# InterfacesB_NONISO232a.net
KiCad netlist of a schematic drawn in Altium Designer
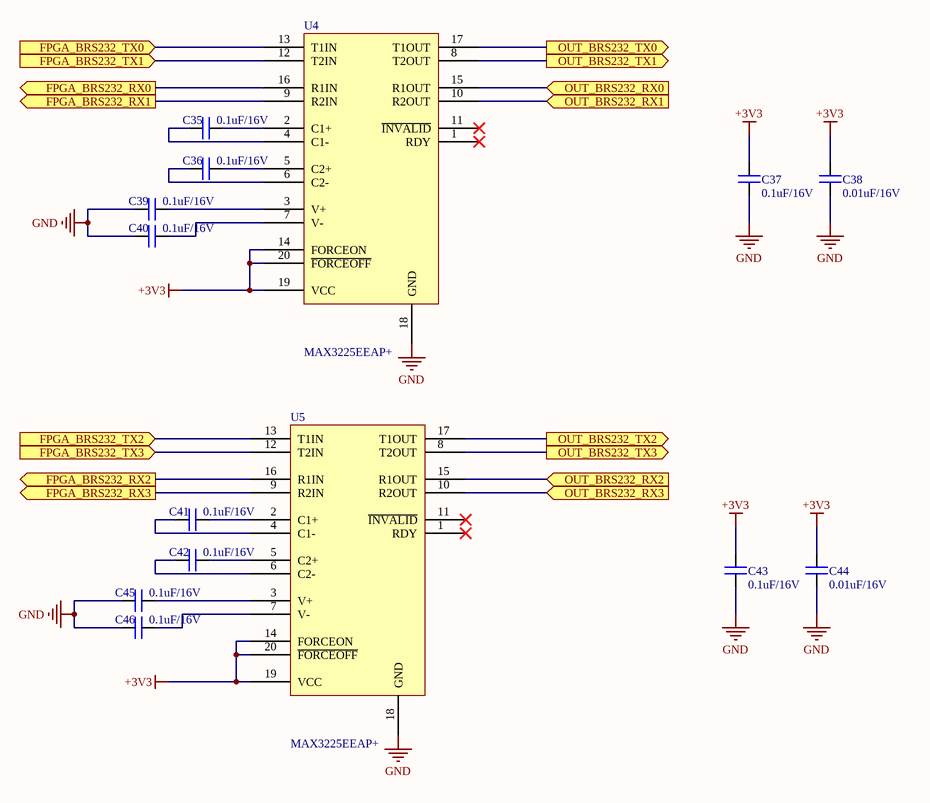
[diagram p0: InterfacesB_NONISO232a.SchDoc]

(export (version "E")
  (design (tool "Eeschema 10.0.6"))
  (components
    (comp (ref "C35")
      (value "0.1uF/16V")
      (footprint "CAP_0805")
      (fields (field (name "Comment") "CAP_0805"))
      (libsource (lib "AdapterLib") (part "CAP_0805"))
    )
    (comp (ref "C36")
      (value "0.1uF/16V")
      (footprint "CAP_0805")
      (fields (field (name "Comment") "CAP_0805"))
      (libsource (lib "AdapterLib") (part "CAP_0805"))
    )
    (comp (ref "C37")
      (value "0.1uF/16V")
      (footprint "CAP_0805")
      (fields (field (name "Comment") "CAP_0805"))
      (libsource (lib "AdapterLib") (part "CAP_0805"))
    )
    (comp (ref "C38")
      (value "0.01uF/16V")
      (footprint "CAP_0805")
      (fields (field (name "Comment") "CAP_0805"))
      (libsource (lib "AdapterLib") (part "CAP_0805"))
    )
    (comp (ref "C39")
      (value "0.1uF/16V")
      (footprint "CAP_0805")
      (fields (field (name "Comment") "CAP_0805"))
      (libsource (lib "AdapterLib") (part "CAP_0805"))
    )
    (comp (ref "C40")
      (value "0.1uF/16V")
      (footprint "CAP_0805")
      (fields (field (name "Comment") "CAP_0805"))
      (libsource (lib "AdapterLib") (part "CAP_0805"))
    )
    (comp (ref "C41")
      (value "0.1uF/16V")
      (footprint "CAP_0805")
      (fields (field (name "Comment") "CAP_0805"))
      (libsource (lib "AdapterLib") (part "CAP_0805"))
    )
    (comp (ref "C42")
      (value "0.1uF/16V")
      (footprint "CAP_0805")
      (fields (field (name "Comment") "CAP_0805"))
      (libsource (lib "AdapterLib") (part "CAP_0805"))
    )
    (comp (ref "C43")
      (value "0.1uF/16V")
      (footprint "CAP_0805")
      (fields (field (name "Comment") "CAP_0805"))
      (libsource (lib "AdapterLib") (part "CAP_0805"))
    )
    (comp (ref "C44")
      (value "0.01uF/16V")
      (footprint "CAP_0805")
      (fields (field (name "Comment") "CAP_0805"))
      (libsource (lib "AdapterLib") (part "CAP_0805"))
    )
    (comp (ref "C45")
      (value "0.1uF/16V")
      (footprint "CAP_0805")
      (fields (field (name "Comment") "CAP_0805"))
      (libsource (lib "AdapterLib") (part "CAP_0805"))
    )
    (comp (ref "C46")
      (value "0.1uF/16V")
      (footprint "CAP_0805")
      (fields (field (name "Comment") "CAP_0805"))
      (libsource (lib "AdapterLib") (part "CAP_0805"))
    )
    (comp (ref "U4")
      (value "MAX3225EEAP+")
      (footprint "MAX3225EEAP+")
      (libsource (lib "AdapterLib") (part "MAX3225EEAP+"))
    )
    (comp (ref "U5")
      (value "MAX3225EEAP+")
      (footprint "MAX3225EEAP+")
      (libsource (lib "AdapterLib") (part "MAX3225EEAP+"))
    )
  )
  (nets
    (net (code "1") (name "+3V3") (class "Default")
      (node (ref "C37") (pin "1") (pinfunction "1_1") (pintype "passive"))
      (node (ref "C38") (pin "1") (pinfunction "1_1") (pintype "passive"))
      (node (ref "C43") (pin "1") (pinfunction "1_1") (pintype "passive"))
      (node (ref "C44") (pin "1") (pinfunction "1_1") (pintype "passive"))
      (node (ref "U4") (pin "14") (pinfunction "FORCEON_14") (pintype "passive"))
      (node (ref "U4") (pin "19") (pinfunction "VCC_19") (pintype "passive"))
      (node (ref "U4") (pin "20") (pinfunction "~{FORCEOFF}_20") (pintype "passive"))
      (node (ref "U5") (pin "14") (pinfunction "FORCEON_14") (pintype "passive"))
      (node (ref "U5") (pin "19") (pinfunction "VCC_19") (pintype "passive"))
      (node (ref "U5") (pin "20") (pinfunction "~{FORCEOFF}_20") (pintype "passive"))
    )
    (net (code "2") (name "/FPGA_BRS232_RX0") (class "Default")
      (node (ref "U4") (pin "16") (pinfunction "R1IN_16") (pintype "passive"))
    )
    (net (code "3") (name "/FPGA_BRS232_RX1") (class "Default")
      (node (ref "U4") (pin "9") (pinfunction "R2IN_9") (pintype "passive"))
    )
    (net (code "4") (name "/FPGA_BRS232_RX2") (class "Default")
      (node (ref "U5") (pin "16") (pinfunction "R1IN_16") (pintype "passive"))
    )
    (net (code "5") (name "/FPGA_BRS232_RX3") (class "Default")
      (node (ref "U5") (pin "9") (pinfunction "R2IN_9") (pintype "passive"))
    )
    (net (code "6") (name "/FPGA_BRS232_TX0") (class "Default")
      (node (ref "U4") (pin "13") (pinfunction "T1IN_13") (pintype "passive"))
    )
    (net (code "7") (name "/FPGA_BRS232_TX1") (class "Default")
      (node (ref "U4") (pin "12") (pinfunction "T2IN_12") (pintype "passive"))
    )
    (net (code "8") (name "/FPGA_BRS232_TX2") (class "Default")
      (node (ref "U5") (pin "13") (pinfunction "T1IN_13") (pintype "passive"))
    )
    (net (code "9") (name "/FPGA_BRS232_TX3") (class "Default")
      (node (ref "U5") (pin "12") (pinfunction "T2IN_12") (pintype "passive"))
    )
    (net (code "10") (name "/OUT_BRS232_RX0") (class "Default")
      (node (ref "U4") (pin "15") (pinfunction "R1OUT_15") (pintype "passive"))
    )
    (net (code "11") (name "/OUT_BRS232_RX1") (class "Default")
      (node (ref "U4") (pin "10") (pinfunction "R2OUT_10") (pintype "passive"))
    )
    (net (code "12") (name "/OUT_BRS232_RX2") (class "Default")
      (node (ref "U5") (pin "15") (pinfunction "R1OUT_15") (pintype "passive"))
    )
    (net (code "13") (name "/OUT_BRS232_RX3") (class "Default")
      (node (ref "U5") (pin "10") (pinfunction "R2OUT_10") (pintype "passive"))
    )
    (net (code "14") (name "/OUT_BRS232_TX0") (class "Default")
      (node (ref "U4") (pin "17") (pinfunction "T1OUT_17") (pintype "passive"))
    )
    (net (code "15") (name "/OUT_BRS232_TX1") (class "Default")
      (node (ref "U4") (pin "8") (pinfunction "T2OUT_8") (pintype "passive"))
    )
    (net (code "16") (name "/OUT_BRS232_TX2") (class "Default")
      (node (ref "U5") (pin "17") (pinfunction "T1OUT_17") (pintype "passive"))
    )
    (net (code "17") (name "/OUT_BRS232_TX3") (class "Default")
      (node (ref "U5") (pin "8") (pinfunction "T2OUT_8") (pintype "passive"))
    )
    (net (code "18") (name "GND") (class "Default")
      (node (ref "C37") (pin "2") (pinfunction "2_2") (pintype "passive"))
      (node (ref "C38") (pin "2") (pinfunction "2_2") (pintype "passive"))
      (node (ref "C39") (pin "2") (pinfunction "2_2") (pintype "passive"))
      (node (ref "C40") (pin "2") (pinfunction "2_2") (pintype "passive"))
      (node (ref "C43") (pin "2") (pinfunction "2_2") (pintype "passive"))
      (node (ref "C44") (pin "2") (pinfunction "2_2") (pintype "passive"))
      (node (ref "C45") (pin "2") (pinfunction "2_2") (pintype "passive"))
      (node (ref "C46") (pin "2") (pinfunction "2_2") (pintype "passive"))
      (node (ref "U4") (pin "18") (pinfunction "GND_18") (pintype "passive"))
      (node (ref "U5") (pin "18") (pinfunction "GND_18") (pintype "passive"))
    )
    (net (code "19") (name "Net-(U4-C1+)") (class "Default")
      (node (ref "C35") (pin "1") (pinfunction "1_1") (pintype "passive"))
      (node (ref "U4") (pin "2") (pinfunction "C1+_2") (pintype "passive"))
    )
    (net (code "20") (name "Net-(U4-C1-)") (class "Default")
      (node (ref "C35") (pin "2") (pinfunction "2_2") (pintype "passive"))
      (node (ref "U4") (pin "4") (pinfunction "C1-_4") (pintype "passive"))
    )
    (net (code "21") (name "Net-(U4-C2+)") (class "Default")
      (node (ref "C36") (pin "1") (pinfunction "1_1") (pintype "passive"))
      (node (ref "U4") (pin "5") (pinfunction "C2+_5") (pintype "passive"))
    )
    (net (code "22") (name "Net-(U4-C2-)") (class "Default")
      (node (ref "C36") (pin "2") (pinfunction "2_2") (pintype "passive"))
      (node (ref "U4") (pin "6") (pinfunction "C2-_6") (pintype "passive"))
    )
    (net (code "23") (name "Net-(U4-V+)") (class "Default")
      (node (ref "C39") (pin "1") (pinfunction "1_1") (pintype "passive"))
      (node (ref "U4") (pin "3") (pinfunction "V+_3") (pintype "passive"))
    )
    (net (code "24") (name "Net-(U4-V-)") (class "Default")
      (node (ref "C40") (pin "1") (pinfunction "1_1") (pintype "passive"))
      (node (ref "U4") (pin "7") (pinfunction "V-_7") (pintype "passive"))
    )
    (net (code "25") (name "Net-(U5-C1+)") (class "Default")
      (node (ref "C41") (pin "1") (pinfunction "1_1") (pintype "passive"))
      (node (ref "U5") (pin "2") (pinfunction "C1+_2") (pintype "passive"))
    )
    (net (code "26") (name "Net-(U5-C1-)") (class "Default")
      (node (ref "C41") (pin "2") (pinfunction "2_2") (pintype "passive"))
      (node (ref "U5") (pin "4") (pinfunction "C1-_4") (pintype "passive"))
    )
    (net (code "27") (name "Net-(U5-C2+)") (class "Default")
      (node (ref "C42") (pin "1") (pinfunction "1_1") (pintype "passive"))
      (node (ref "U5") (pin "5") (pinfunction "C2+_5") (pintype "passive"))
    )
    (net (code "28") (name "Net-(U5-C2-)") (class "Default")
      (node (ref "C42") (pin "2") (pinfunction "2_2") (pintype "passive"))
      (node (ref "U5") (pin "6") (pinfunction "C2-_6") (pintype "passive"))
    )
    (net (code "29") (name "Net-(U5-V+)") (class "Default")
      (node (ref "C45") (pin "1") (pinfunction "1_1") (pintype "passive"))
      (node (ref "U5") (pin "3") (pinfunction "V+_3") (pintype "passive"))
    )
    (net (code "30") (name "Net-(U5-V-)") (class "Default")
      (node (ref "C46") (pin "1") (pinfunction "1_1") (pintype "passive"))
      (node (ref "U5") (pin "7") (pinfunction "V-_7") (pintype "passive"))
    )
    (net (code "31") (name "unconnected-(U4-RDY-Pad1)") (class "Default")
      (node (ref "U4") (pin "1") (pinfunction "RDY_1") (pintype "passive+no_connect"))
    )
    (net (code "32") (name "unconnected-(U4-~{INVALID}-Pad11)") (class "Default")
      (node (ref "U4") (pin "11") (pinfunction "~{INVALID}_11") (pintype "passive+no_connect"))
    )
    (net (code "33") (name "unconnected-(U5-RDY-Pad1)") (class "Default")
      (node (ref "U5") (pin "1") (pinfunction "RDY_1") (pintype "passive+no_connect"))
    )
    (net (code "34") (name "unconnected-(U5-~{INVALID}-Pad11)") (class "Default")
      (node (ref "U5") (pin "11") (pinfunction "~{INVALID}_11") (pintype "passive+no_connect"))
    )
  )
)
